# sensorboard.net
KiCad netlist of a schematic drawn in EAGLE
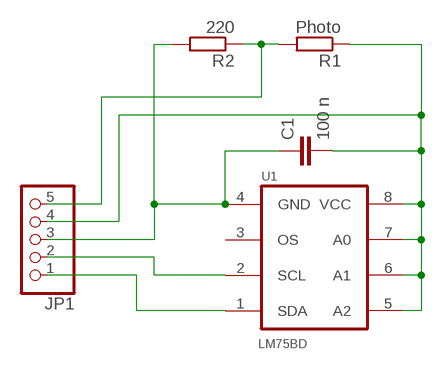
[diagram p0: schematic, sheet 1]

(export (version "E")
  (design (tool "Eeschema 10.0.6"))
  (components
    (comp (ref "C1")
      (value "100 n")
      (footprint "eagle-import:C0805")
      (libsource (lib "eagle-import") (part "C-EUC0805"))
    )
    (comp (ref "JP1")
      (value "PINHD-1X5/90")
      (footprint "eagle-import:1X05_90")
      (libsource (lib "eagle-import") (part "PINHD-1X5/90"))
    )
    (comp (ref "R1")
      (value "Photo")
      (footprint "eagle-import:0207_15")
      (libsource (lib "eagle-import") (part "R-EU_0207/15"))
    )
    (comp (ref "R2")
      (value "220")
      (footprint "eagle-import:R0805")
      (libsource (lib "eagle-import") (part "R-EU_R0805"))
    )
    (comp (ref "U1")
      (value "LM75BD")
      (footprint "eagle-import:SOIC127P600X175-8N")
      (libsource (lib "eagle-import") (part "LM75BD"))
    )
  )
  (nets
    (net (code "1") (name "Net-(JP1-Pad5)") (class "Default")
      (node (ref "JP1") (pin "5") (pinfunction "5_5") (pintype "passive"))
      (node (ref "R1") (pin "2") (pinfunction "2_2") (pintype "passive"))
      (node (ref "R2") (pin "1") (pinfunction "1_1") (pintype "passive"))
    )
    (net (code "2") (name "Net-(U1-A0)") (class "Default")
      (node (ref "C1") (pin "2") (pinfunction "2_2") (pintype "passive"))
      (node (ref "JP1") (pin "4") (pinfunction "4_4") (pintype "passive"))
      (node (ref "R1") (pin "1") (pinfunction "1_1") (pintype "passive"))
      (node (ref "U1") (pin "5") (pinfunction "A2_5") (pintype "input"))
      (node (ref "U1") (pin "6") (pinfunction "A1_6") (pintype "input"))
      (node (ref "U1") (pin "7") (pinfunction "A0_7") (pintype "input"))
      (node (ref "U1") (pin "8") (pinfunction "VCC_8") (pintype "power_in"))
    )
    (net (code "3") (name "Net-(U1-GND)") (class "Default")
      (node (ref "C1") (pin "1") (pinfunction "1_1") (pintype "passive"))
      (node (ref "JP1") (pin "3") (pinfunction "3_3") (pintype "passive"))
      (node (ref "R2") (pin "2") (pinfunction "2_2") (pintype "passive"))
      (node (ref "U1") (pin "4") (pinfunction "GND_4") (pintype "passive"))
    )
    (net (code "4") (name "Net-(U1-SCL)") (class "Default")
      (node (ref "JP1") (pin "2") (pinfunction "2_2") (pintype "passive"))
      (node (ref "U1") (pin "2") (pinfunction "SCL_2") (pintype "input"))
    )
    (net (code "5") (name "Net-(U1-SDA)") (class "Default")
      (node (ref "JP1") (pin "1") (pinfunction "1_1") (pintype "passive"))
      (node (ref "U1") (pin "1") (pinfunction "SDA_1") (pintype "bidirectional"))
    )
    (net (code "6") (name "unconnected-(U1-OS-Pad3)") (class "Default")
      (node (ref "U1") (pin "3") (pinfunction "OS_3") (pintype "output"))
    )
  )
)
